# stlink_v3_spi_flasher_shield.net
KiCad netlist of a schematic drawn in EAGLE
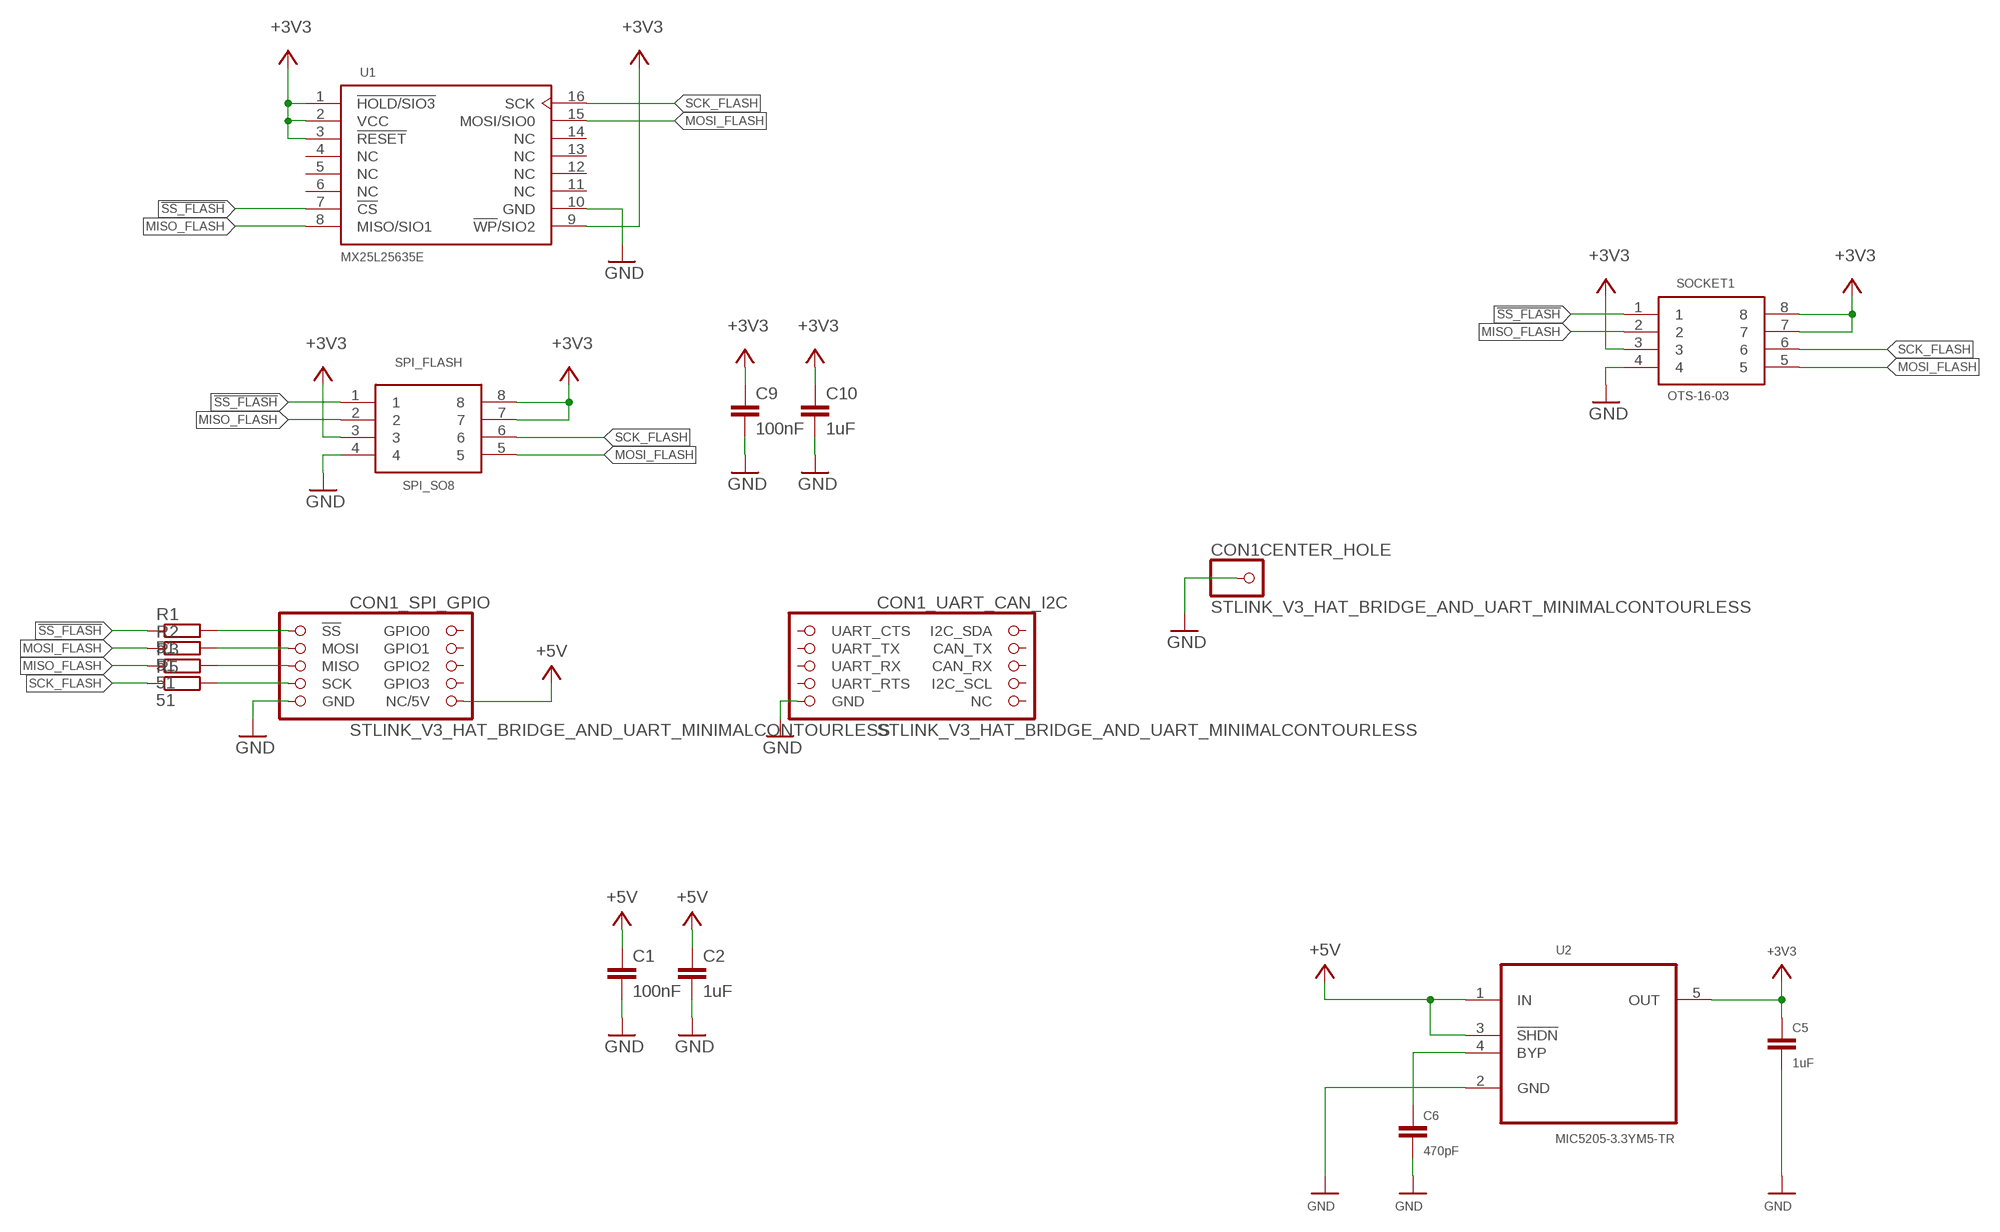
[diagram p0: schematic, sheet 1]

(export (version "E")
  (design (tool "Eeschema 10.0.6"))
  (components
    (comp (ref "C1")
      (value "100nF")
      (footprint "eagle-import:C0603")
      (libsource (lib "eagle-import") (part "C-EUC0603"))
    )
    (comp (ref "C2")
      (value "1uF")
      (footprint "eagle-import:C0603")
      (libsource (lib "eagle-import") (part "C-EUC0603"))
    )
    (comp (ref "C5")
      (value "1uF")
      (footprint "eagle-import:C0603")
      (libsource (lib "eagle-import") (part "C-EUC0603"))
    )
    (comp (ref "C6")
      (value "470pF")
      (footprint "eagle-import:C0603")
      (libsource (lib "eagle-import") (part "C-EUC0603"))
    )
    (comp (ref "C9")
      (value "100nF")
      (footprint "eagle-import:C0603")
      (libsource (lib "eagle-import") (part "C-EUC0603"))
    )
    (comp (ref "C10")
      (value "1uF")
      (footprint "eagle-import:C0603")
      (libsource (lib "eagle-import") (part "C-EUC0603"))
    )
    (comp (ref "CON1")
      (value "STLINK_V3_HAT_BRIDGE_AND_UART_MINIMALCONTOURLESS")
      (footprint "eagle-import:STLINKV3_HAT_BRIDGE_MINIMAL_CONTOURLESS")
      (libsource (lib "eagle-import") (part "STLINK_V3_HAT_BRIDGE_AND_UART_MINIMALCONTOURLESS"))
    )
    (comp (ref "R1")
      (value "51")
      (footprint "eagle-import:R0603")
      (libsource (lib "eagle-import") (part "R-EU_R0603"))
    )
    (comp (ref "R2")
      (value "51")
      (footprint "eagle-import:R0603")
      (libsource (lib "eagle-import") (part "R-EU_R0603"))
    )
    (comp (ref "R3")
      (value "51")
      (footprint "eagle-import:R0603")
      (libsource (lib "eagle-import") (part "R-EU_R0603"))
    )
    (comp (ref "R5")
      (value "51")
      (footprint "eagle-import:R0603")
      (libsource (lib "eagle-import") (part "R-EU_R0603"))
    )
    (comp (ref "SOCKET1")
      (value "OTS-16-03")
      (footprint "eagle-import:OTS-16-03")
      (libsource (lib "eagle-import") (part "OTS-16-03"))
    )
    (comp (ref "SPI_FLASH")
      (value "SPI_SO8")
      (footprint "eagle-import:SO8_LONG")
      (libsource (lib "eagle-import") (part "SO8_LONG"))
    )
    (comp (ref "U1")
      (value "MX25L25635E")
      (footprint "eagle-import:SOP127P780X200-16N")
      (libsource (lib "eagle-import") (part "MX25L25635E"))
    )
    (comp (ref "U2")
      (value "MIC5205-3.3YM5-TR")
      (footprint "eagle-import:SOT95P280X145-5N")
      (fields (field (name "MPN") "LT1761ES5-3.3#TRMPBF"))
      (libsource (lib "eagle-import") (part "LT1761ES5-3.3TRMPBF"))
    )
  )
  (nets
    (net (code "1") (name "+3V3") (class "Default")
      (node (ref "C10") (pin "1") (pinfunction "1_1") (pintype "passive"))
      (node (ref "C5") (pin "1") (pinfunction "1_1") (pintype "passive"))
      (node (ref "C9") (pin "1") (pinfunction "1_1") (pintype "passive"))
      (node (ref "SOCKET1") (pin "3") (pinfunction "3_3") (pintype "bidirectional"))
      (node (ref "SOCKET1") (pin "7") (pinfunction "7_7") (pintype "bidirectional"))
      (node (ref "SOCKET1") (pin "8") (pinfunction "8_8") (pintype "bidirectional"))
      (node (ref "SPI_FLASH") (pin "3") (pinfunction "3_3") (pintype "bidirectional"))
      (node (ref "SPI_FLASH") (pin "7") (pinfunction "7_7") (pintype "bidirectional"))
      (node (ref "SPI_FLASH") (pin "8") (pinfunction "8_8") (pintype "bidirectional"))
      (node (ref "U1") (pin "1") (pinfunction "~{HOLD/SIO3}_1") (pintype "input"))
      (node (ref "U1") (pin "2") (pinfunction "VCC_2") (pintype "passive"))
      (node (ref "U1") (pin "3") (pinfunction "~{RESET}_3") (pintype "input"))
      (node (ref "U1") (pin "9") (pinfunction "~{WP}/SIO2_9") (pintype "bidirectional"))
      (node (ref "U2") (pin "5") (pinfunction "OUT_5") (pintype "passive"))
    )
    (net (code "2") (name "+5V") (class "Default")
      (node (ref "C1") (pin "1") (pinfunction "1_1") (pintype "passive"))
      (node (ref "C2") (pin "1") (pinfunction "1_1") (pintype "passive"))
      (node (ref "CON1") (pin "SPI_10") (pinfunction "NC/5V_SPI_10") (pintype "power_in"))
      (node (ref "U2") (pin "1") (pinfunction "IN_1") (pintype "passive"))
      (node (ref "U2") (pin "3") (pinfunction "~{SHDN}_3") (pintype "input"))
    )
    (net (code "3") (name "/~{SS_FLASH}") (class "Default")
      (node (ref "R1") (pin "1") (pinfunction "1_1") (pintype "passive"))
      (node (ref "SOCKET1") (pin "1") (pinfunction "1_1") (pintype "bidirectional"))
      (node (ref "SPI_FLASH") (pin "1") (pinfunction "1_1") (pintype "bidirectional"))
      (node (ref "U1") (pin "7") (pinfunction "~{CS}_7") (pintype "input"))
    )
    (net (code "4") (name "GND") (class "Default")
      (node (ref "C1") (pin "2") (pinfunction "2_2") (pintype "passive"))
      (node (ref "C10") (pin "2") (pinfunction "2_2") (pintype "passive"))
      (node (ref "C2") (pin "2") (pinfunction "2_2") (pintype "passive"))
      (node (ref "C5") (pin "2") (pinfunction "2_2") (pintype "passive"))
      (node (ref "C6") (pin "2") (pinfunction "2_2") (pintype "passive"))
      (node (ref "C9") (pin "2") (pinfunction "2_2") (pintype "passive"))
      (node (ref "CON1") (pin "CENTER") (pinfunction "1_CENTER") (pintype "passive"))
      (node (ref "CON1") (pin "SPI_9") (pinfunction "GND_SPI_9") (pintype "passive"))
      (node (ref "CON1") (pin "UART_9") (pinfunction "GND_UART_9") (pintype "passive"))
      (node (ref "SOCKET1") (pin "4") (pinfunction "4_4") (pintype "bidirectional"))
      (node (ref "SPI_FLASH") (pin "4") (pinfunction "4_4") (pintype "bidirectional"))
      (node (ref "U1") (pin "10") (pinfunction "GND_10") (pintype "passive"))
      (node (ref "U2") (pin "2") (pinfunction "GND_2") (pintype "passive"))
    )
    (net (code "5") (name "MISO_FLASH") (class "Default")
      (node (ref "R3") (pin "1") (pinfunction "1_1") (pintype "passive"))
      (node (ref "SOCKET1") (pin "2") (pinfunction "2_2") (pintype "bidirectional"))
      (node (ref "SPI_FLASH") (pin "2") (pinfunction "2_2") (pintype "bidirectional"))
      (node (ref "U1") (pin "8") (pinfunction "MISO/SIO1_8") (pintype "output"))
    )
    (net (code "6") (name "MOSI_FLASH") (class "Default")
      (node (ref "R2") (pin "1") (pinfunction "1_1") (pintype "passive"))
      (node (ref "SOCKET1") (pin "5") (pinfunction "5_5") (pintype "bidirectional"))
      (node (ref "SPI_FLASH") (pin "5") (pinfunction "5_5") (pintype "bidirectional"))
      (node (ref "U1") (pin "15") (pinfunction "MOSI/SIO0_15") (pintype "input"))
    )
    (net (code "7") (name "Net-(CON1B-MISO)") (class "Default")
      (node (ref "CON1") (pin "SPI_5") (pinfunction "MISO_SPI_5") (pintype "input"))
      (node (ref "R3") (pin "2") (pinfunction "2_2") (pintype "passive"))
    )
    (net (code "8") (name "Net-(CON1B-MOSI)") (class "Default")
      (node (ref "CON1") (pin "SPI_3") (pinfunction "MOSI_SPI_3") (pintype "output"))
      (node (ref "R2") (pin "2") (pinfunction "2_2") (pintype "passive"))
    )
    (net (code "9") (name "Net-(CON1B-SCK)") (class "Default")
      (node (ref "CON1") (pin "SPI_7") (pinfunction "SCK_SPI_7") (pintype "output"))
      (node (ref "R5") (pin "2") (pinfunction "2_2") (pintype "passive"))
    )
    (net (code "10") (name "Net-(CON1B-~{SS})") (class "Default")
      (node (ref "CON1") (pin "SPI_1") (pinfunction "~{SS}_SPI_1") (pintype "output"))
      (node (ref "R1") (pin "2") (pinfunction "2_2") (pintype "passive"))
    )
    (net (code "11") (name "Net-(U2-BYP)") (class "Default")
      (node (ref "C6") (pin "1") (pinfunction "1_1") (pintype "passive"))
      (node (ref "U2") (pin "4") (pinfunction "BYP_4") (pintype "passive"))
    )
    (net (code "12") (name "SCK_FLASH") (class "Default")
      (node (ref "R5") (pin "1") (pinfunction "1_1") (pintype "passive"))
      (node (ref "SOCKET1") (pin "6") (pinfunction "6_6") (pintype "bidirectional"))
      (node (ref "SPI_FLASH") (pin "6") (pinfunction "6_6") (pintype "bidirectional"))
      (node (ref "U1") (pin "16") (pinfunction "SCK_16") (pintype "input"))
    )
    (net (code "13") (name "unconnected-(CON1B-GPIO0-PadSPI_2)") (class "Default")
      (node (ref "CON1") (pin "SPI_2") (pinfunction "GPIO0_SPI_2") (pintype "bidirectional"))
    )
    (net (code "14") (name "unconnected-(CON1B-GPIO1-PadSPI_4)") (class "Default")
      (node (ref "CON1") (pin "SPI_4") (pinfunction "GPIO1_SPI_4") (pintype "bidirectional"))
    )
    (net (code "15") (name "unconnected-(CON1B-GPIO2-PadSPI_6)") (class "Default")
      (node (ref "CON1") (pin "SPI_6") (pinfunction "GPIO2_SPI_6") (pintype "bidirectional"))
    )
    (net (code "16") (name "unconnected-(CON1B-GPIO3-PadSPI_8)") (class "Default")
      (node (ref "CON1") (pin "SPI_8") (pinfunction "GPIO3_SPI_8") (pintype "bidirectional"))
    )
    (net (code "17") (name "unconnected-(CON1C-CAN_RX-PadUART_6)") (class "Default")
      (node (ref "CON1") (pin "UART_6") (pinfunction "CAN_RX_UART_6") (pintype "input"))
    )
    (net (code "18") (name "unconnected-(CON1C-CAN_TX-PadUART_4)") (class "Default")
      (node (ref "CON1") (pin "UART_4") (pinfunction "CAN_TX_UART_4") (pintype "output"))
    )
    (net (code "19") (name "unconnected-(CON1C-I2C_SCL-PadUART_8)") (class "Default")
      (node (ref "CON1") (pin "UART_8") (pinfunction "I2C_SCL_UART_8") (pintype "open_collector"))
    )
    (net (code "20") (name "unconnected-(CON1C-I2C_SDA-PadUART_2)") (class "Default")
      (node (ref "CON1") (pin "UART_2") (pinfunction "I2C_SDA_UART_2") (pintype "open_collector"))
    )
    (net (code "21") (name "unconnected-(CON1C-NC-PadUART_10)") (class "Default")
      (node (ref "CON1") (pin "UART_10") (pinfunction "NC_UART_10") (pintype "no_connect"))
    )
    (net (code "22") (name "unconnected-(CON1C-UART_CTS-PadUART_1)") (class "Default")
      (node (ref "CON1") (pin "UART_1") (pinfunction "UART_CTS_UART_1") (pintype "input"))
    )
    (net (code "23") (name "unconnected-(CON1C-UART_RTS-PadUART_7)") (class "Default")
      (node (ref "CON1") (pin "UART_7") (pinfunction "UART_RTS_UART_7") (pintype "output"))
    )
    (net (code "24") (name "unconnected-(CON1C-UART_RX-PadUART_5)") (class "Default")
      (node (ref "CON1") (pin "UART_5") (pinfunction "UART_RX_UART_5") (pintype "input"))
    )
    (net (code "25") (name "unconnected-(CON1C-UART_TX-PadUART_3)") (class "Default")
      (node (ref "CON1") (pin "UART_3") (pinfunction "UART_TX_UART_3") (pintype "output"))
    )
    (net (code "26") (name "unconnected-(U1-NC-Pad4)") (class "Default")
      (node (ref "U1") (pin "4") (pinfunction "NC_4") (pintype "no_connect"))
    )
    (net (code "27") (name "unconnected-(U1-NC-Pad5)") (class "Default")
      (node (ref "U1") (pin "5") (pinfunction "NC_5") (pintype "no_connect"))
    )
    (net (code "28") (name "unconnected-(U1-NC-Pad6)") (class "Default")
      (node (ref "U1") (pin "6") (pinfunction "NC_6") (pintype "no_connect"))
    )
    (net (code "29") (name "unconnected-(U1-NC-Pad11)") (class "Default")
      (node (ref "U1") (pin "11") (pinfunction "NC_11") (pintype "no_connect"))
    )
    (net (code "30") (name "unconnected-(U1-NC-Pad12)") (class "Default")
      (node (ref "U1") (pin "12") (pinfunction "NC_12") (pintype "no_connect"))
    )
    (net (code "31") (name "unconnected-(U1-NC-Pad13)") (class "Default")
      (node (ref "U1") (pin "13") (pinfunction "NC_13") (pintype "no_connect"))
    )
    (net (code "32") (name "unconnected-(U1-NC-Pad14)") (class "Default")
      (node (ref "U1") (pin "14") (pinfunction "NC_14") (pintype "no_connect"))
    )
  )
)
